# Temp.net
KiCad netlist of a schematic drawn in Altium Designer
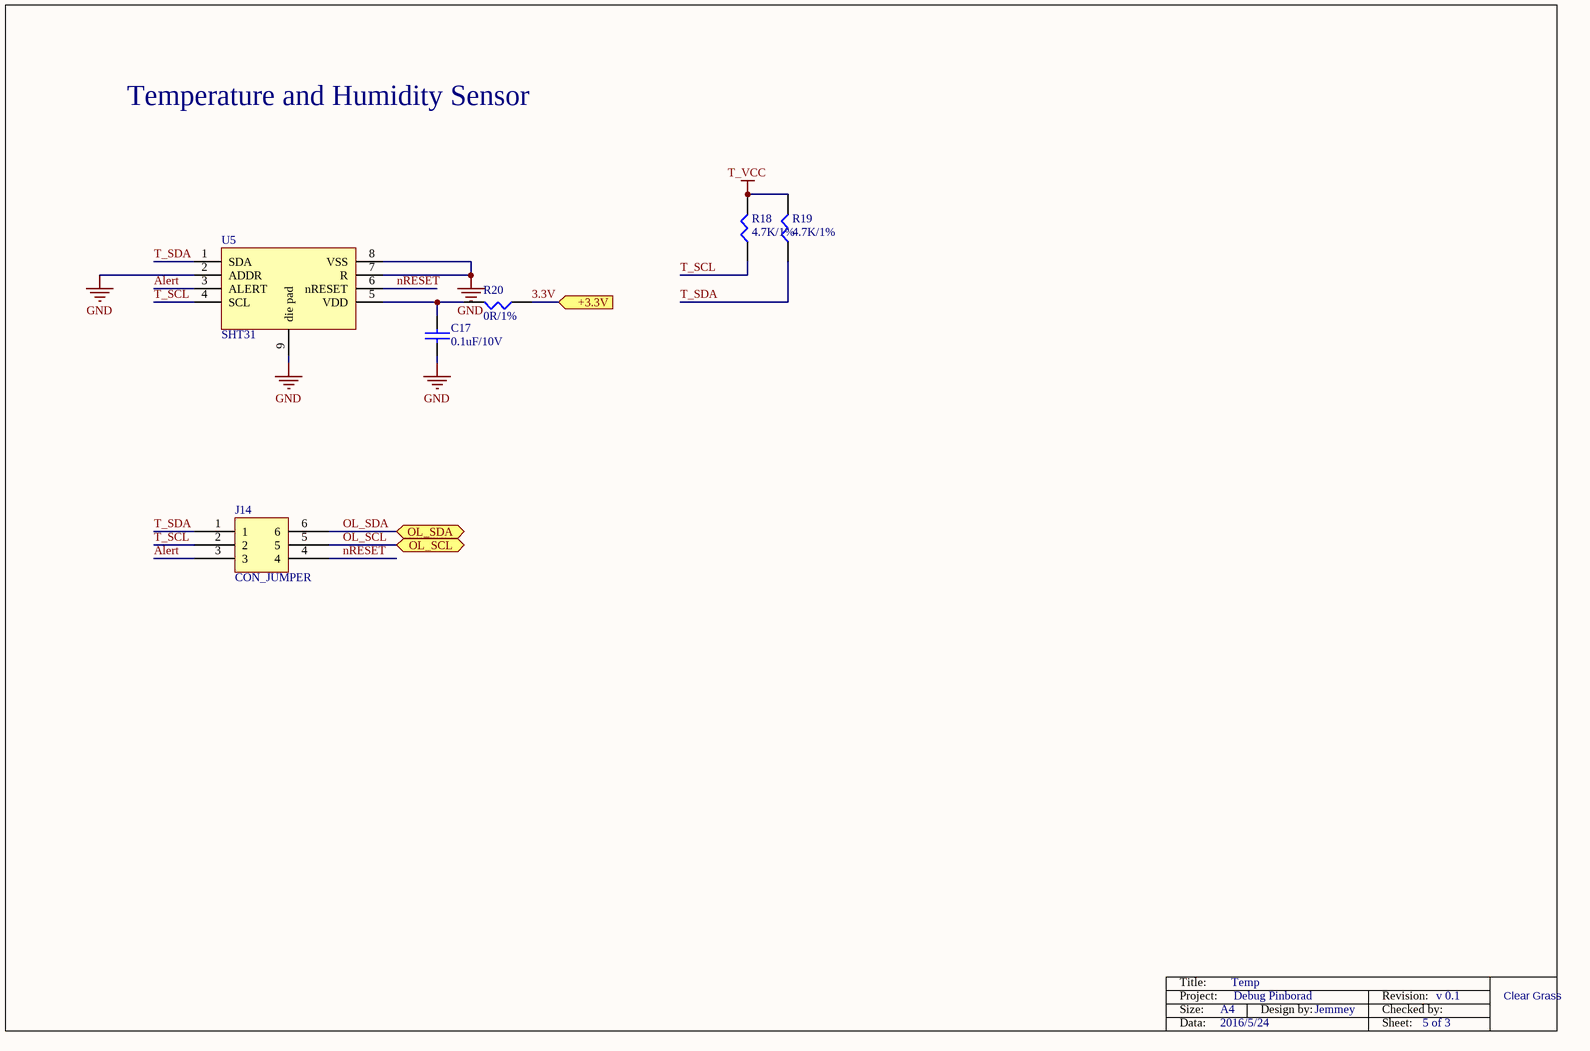
[diagram p0: Temp.SchDoc]

(export (version "E")
  (design (tool "Eeschema 10.0.6"))
  (components
    (comp (ref "C17")
      (value "0.1uF/10V")
      (footprint "0402C")
      (description "厂家：Murata，型号：GRM155R71A104KA01D")
      (libsource (lib "*") (part "CAP"))
    )
    (comp (ref "J14") (value "CON_JUMPER") (libsource (lib "Debug Pinborad") (part "CON_JUMPER")))
    (comp (ref "R18")
      (value "4.7K/1%")
      (footprint "0402R")
      (description "厂家：Yageo，型号：RC0402FR-0710KL")
      (libsource (lib "*") (part "RES1"))
    )
    (comp (ref "R19")
      (value "4.7K/1%")
      (footprint "0402R")
      (description "厂家：Yageo，型号：RC0402FR-0710KL")
      (libsource (lib "*") (part "RES1"))
    )
    (comp (ref "R20")
      (value "0R/1%")
      (footprint "0402R")
      (description "厂家：Yageo，型号：RC0402FR-0710KL")
      (libsource (lib "*") (part "RES1"))
    )
    (comp (ref "U5")
      (value "SHT31")
      (footprint "DFN")
      (description "厂家：盛思睿，型号：SHT31")
      (libsource (lib "Temp Sensirion assy FPC") (part "SHT31"))
    )
  )
  (nets
    (net (code "1") (name "/3.3V") (class "Default")
      (node (ref "R20") (pin "1") (pinfunction "1_1") (pintype "passive"))
    )
    (net (code "2") (name "/Alert") (class "Default")
      (node (ref "J14") (pin "3") (pinfunction "3_3") (pintype "passive"))
      (node (ref "U5") (pin "3") (pinfunction "ALERT_3") (pintype "passive"))
    )
    (net (code "3") (name "/OL_SCL") (class "Default")
      (node (ref "J14") (pin "5") (pinfunction "5_5") (pintype "passive"))
    )
    (net (code "4") (name "/OL_SDA") (class "Default")
      (node (ref "J14") (pin "6") (pinfunction "6_6") (pintype "passive"))
    )
    (net (code "5") (name "/T_SCL") (class "Default")
      (node (ref "J14") (pin "2") (pinfunction "2_2") (pintype "passive"))
      (node (ref "R18") (pin "1") (pinfunction "1_1") (pintype "passive"))
      (node (ref "U5") (pin "4") (pinfunction "SCL_4") (pintype "passive"))
    )
    (net (code "6") (name "/T_SDA") (class "Default")
      (node (ref "J14") (pin "1") (pinfunction "1_1") (pintype "passive"))
      (node (ref "R19") (pin "1") (pinfunction "1_1") (pintype "passive"))
      (node (ref "U5") (pin "1") (pinfunction "SDA_1") (pintype "passive"))
    )
    (net (code "7") (name "/nRESET") (class "Default")
      (node (ref "J14") (pin "4") (pinfunction "4_4") (pintype "passive"))
      (node (ref "U5") (pin "6") (pinfunction "nRESET_6") (pintype "passive"))
    )
    (net (code "8") (name "GND") (class "Default")
      (node (ref "C17") (pin "2") (pinfunction "2_2") (pintype "passive"))
      (node (ref "U5") (pin "2") (pinfunction "ADDR_2") (pintype "passive"))
      (node (ref "U5") (pin "7") (pinfunction "R_7") (pintype "passive"))
      (node (ref "U5") (pin "8") (pinfunction "VSS_8") (pintype "passive"))
      (node (ref "U5") (pin "9") (pinfunction "die_pad_9") (pintype "passive"))
    )
    (net (code "9") (name "Net-(U5-VDD)") (class "Default")
      (node (ref "C17") (pin "1") (pinfunction "1_1") (pintype "passive"))
      (node (ref "R20") (pin "2") (pinfunction "2_2") (pintype "passive"))
      (node (ref "U5") (pin "5") (pinfunction "VDD_5") (pintype "passive"))
    )
    (net (code "10") (name "T_VCC") (class "Default")
      (node (ref "R18") (pin "2") (pinfunction "2_2") (pintype "passive"))
      (node (ref "R19") (pin "2") (pinfunction "2_2") (pintype "passive"))
    )
  )
)
